# InputCircuitsAndSupply.net
KiCad netlist of a schematic drawn in Altium Designer
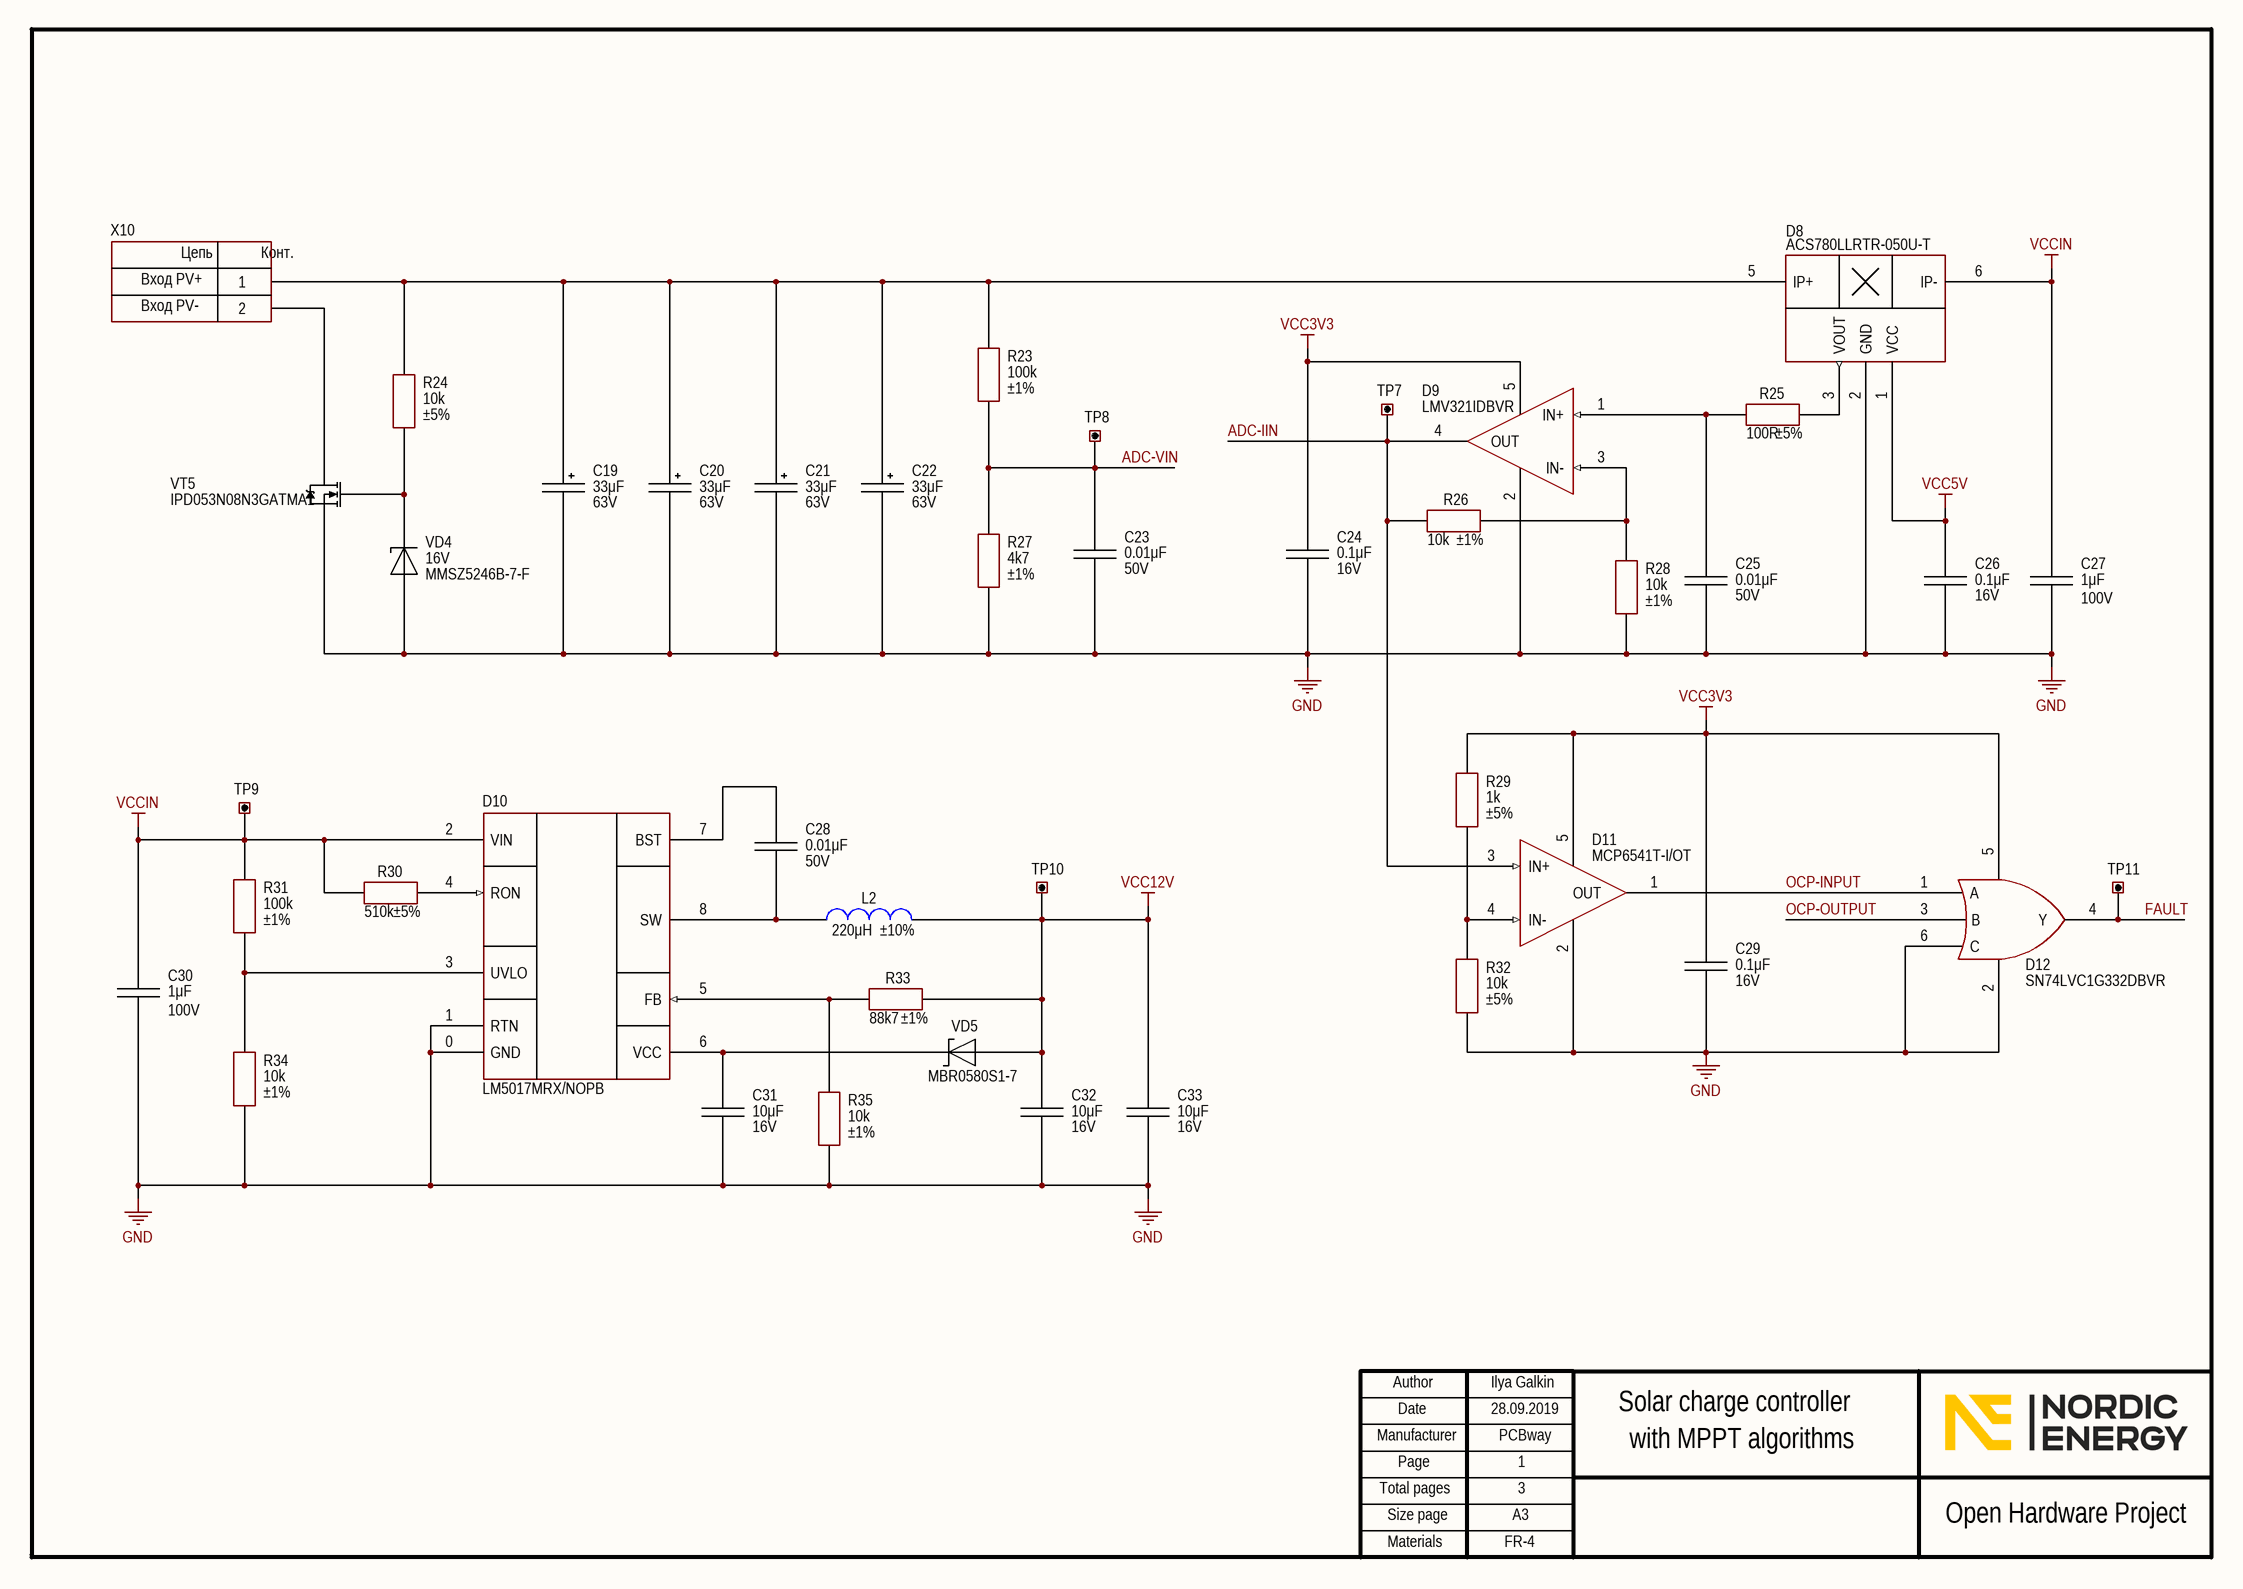
[diagram p0: InputCircuitsAndSupply.SchDoc]

(export (version "E")
  (design (tool "Eeschema 10.0.6"))
  (components
    (comp (ref "C19")
      (value "33μF")
      (footprint "CAP: D8C3.5H12")
      (fields
        (field (name "MANUFACTURER") "Panasonic")
        (field (name "PARTNUMBER") "63SXE33M")
        (field (name "VALUEMANUFACTURERPARTNUMBER") "Aluminium capacitor, 33μF, 63V, ±20%, 25mOhm, 12x8x3.5 mm, -55...+105°C")
        (field (name "VOLTAGE") "63V")
      )
      (libsource (lib "Capacitor") (part "Aluminium"))
    )
    (comp (ref "C20")
      (value "33μF")
      (footprint "CAP: D8C3.5H12")
      (fields
        (field (name "MANUFACTURER") "Panasonic")
        (field (name "PARTNUMBER") "63SXE33M")
        (field (name "VALUEMANUFACTURERPARTNUMBER") "Aluminium capacitor, 33μF, 63V, ±20%, 25mOhm, 12x8x3.5 mm, -55...+105°C")
        (field (name "VOLTAGE") "63V")
      )
      (libsource (lib "Capacitor") (part "Aluminium"))
    )
    (comp (ref "C21")
      (value "33μF")
      (footprint "CAP: D8C3.5H12")
      (fields
        (field (name "MANUFACTURER") "Panasonic")
        (field (name "PARTNUMBER") "63SXE33M")
        (field (name "VALUEMANUFACTURERPARTNUMBER") "Aluminium capacitor, 33μF, 63V, ±20%, 25mOhm, 12x8x3.5 mm, -55...+105°C")
        (field (name "VOLTAGE") "63V")
      )
      (libsource (lib "Capacitor") (part "Aluminium"))
    )
    (comp (ref "C22")
      (value "33μF")
      (footprint "CAP: D8C3.5H12")
      (fields
        (field (name "MANUFACTURER") "Panasonic")
        (field (name "PARTNUMBER") "63SXE33M")
        (field (name "VALUEMANUFACTURERPARTNUMBER") "Aluminium capacitor, 33μF, 63V, ±20%, 25mOhm, 12x8x3.5 mm, -55...+105°C")
        (field (name "VOLTAGE") "63V")
      )
      (libsource (lib "Capacitor") (part "Aluminium"))
    )
    (comp (ref "C23")
      (value "0.01μF")
      (footprint "CAP: 0805")
      (fields
        (field (name "MANUFACTURER") "Yageo")
        (field (name "PARTNUMBER") "CC0805KRX7R9BB103")
        (field (name "VALUEMANUFACTURERPARTNUMBER") "Ceramic capacitor, 0.01μF, X7R, ±10%, 50V, 0805, -55...+125°C")
        (field (name "VOLTAGE") "50V")
      )
      (libsource (lib "Capacitor") (part "Ceramic_0805"))
    )
    (comp (ref "C24")
      (value "0.1μF")
      (footprint "CAP: 0805")
      (fields
        (field (name "MANUFACTURER") "Yageo")
        (field (name "PARTNUMBER") "CC0805KRX7R7BB104")
        (field (name "VALUEMANUFACTURERPARTNUMBER") "Ceramic capacitor, 0.1μF, X7R, ±10%, 16V, 0805, -55...+125°C")
        (field (name "VOLTAGE") "16V")
      )
      (libsource (lib "Capacitor") (part "Ceramic_0805"))
    )
    (comp (ref "C25")
      (value "0.01μF")
      (footprint "CAP: 0805")
      (fields
        (field (name "MANUFACTURER") "Yageo")
        (field (name "PARTNUMBER") "CC0805KRX7R9BB103")
        (field (name "VALUEMANUFACTURERPARTNUMBER") "Ceramic capacitor, 0.01μF, X7R, ±10%, 50V, 0805, -55...+125°C")
        (field (name "VOLTAGE") "50V")
      )
      (libsource (lib "Capacitor") (part "Ceramic_0805"))
    )
    (comp (ref "C26")
      (value "0.1μF")
      (footprint "CAP: 0805")
      (fields
        (field (name "MANUFACTURER") "Yageo")
        (field (name "PARTNUMBER") "CC0805KRX7R7BB104")
        (field (name "VALUEMANUFACTURERPARTNUMBER") "Ceramic capacitor, 0.1μF, X7R, ±10%, 16V, 0805, -55...+125°C")
        (field (name "VOLTAGE") "16V")
      )
      (libsource (lib "Capacitor") (part "Ceramic_0805"))
    )
    (comp (ref "C27")
      (value "1μF")
      (footprint "CAP: 1206")
      (fields
        (field (name "MANUFACTURER") "Samsung")
        (field (name "PARTNUMBER") "CL31B105KCHNNNE")
        (field (name "VALUEMANUFACTURERPARTNUMBER") "Ceramic capacitor, 1μF, X7R, ±10%, 100V, 1206, -55...+125°C")
        (field (name "VOLTAGE") "100V")
      )
      (libsource (lib "Capacitor") (part "Ceramic_1206"))
    )
    (comp (ref "C28")
      (value "0.01μF")
      (footprint "CAP: 0805")
      (fields
        (field (name "MANUFACTURER") "Yageo")
        (field (name "PARTNUMBER") "CC0805KRX7R9BB103")
        (field (name "VALUEMANUFACTURERPARTNUMBER") "Ceramic capacitor, 0.01μF, X7R, ±10%, 50V, 0805, -55...+125°C")
        (field (name "VOLTAGE") "50V")
      )
      (libsource (lib "Capacitor") (part "Ceramic_0805"))
    )
    (comp (ref "C29")
      (value "0.1μF")
      (footprint "CAP: 0805")
      (fields
        (field (name "MANUFACTURER") "Yageo")
        (field (name "PARTNUMBER") "CC0805KRX7R7BB104")
        (field (name "VALUEMANUFACTURERPARTNUMBER") "Ceramic capacitor, 0.1μF, X7R, ±10%, 16V, 0805, -55...+125°C")
        (field (name "VOLTAGE") "16V")
      )
      (libsource (lib "Capacitor") (part "Ceramic_0805"))
    )
    (comp (ref "C30")
      (value "1μF")
      (footprint "CAP: 1206")
      (fields
        (field (name "MANUFACTURER") "Samsung")
        (field (name "PARTNUMBER") "CL31B105KCHNNNE")
        (field (name "VALUEMANUFACTURERPARTNUMBER") "Ceramic capacitor, 1μF, X7R, ±10%, 100V, 1206, -55...+125°C")
        (field (name "VOLTAGE") "100V")
      )
      (libsource (lib "Capacitor") (part "Ceramic_1206"))
    )
    (comp (ref "C31")
      (value "10μF")
      (footprint "CAP: 0805")
      (fields
        (field (name "MANUFACTURER") "Samsung")
        (field (name "PARTNUMBER") "CL21B106KOQNNNG")
        (field (name "VALUEMANUFACTURERPARTNUMBER") "Ceramic capacitor, 10μF, X7R, ±10%, 16V, 0805, -55...+125°C")
        (field (name "VOLTAGE") "16V")
      )
      (libsource (lib "Capacitor") (part "Ceramic_0805"))
    )
    (comp (ref "C32")
      (value "10μF")
      (footprint "CAP: 0805")
      (fields
        (field (name "MANUFACTURER") "Samsung")
        (field (name "PARTNUMBER") "CL21B106KOQNNNG")
        (field (name "VALUEMANUFACTURERPARTNUMBER") "Ceramic capacitor, 10μF, X7R, ±10%, 16V, 0805, -55...+125°C")
        (field (name "VOLTAGE") "16V")
      )
      (libsource (lib "Capacitor") (part "Ceramic_0805"))
    )
    (comp (ref "C33")
      (value "10μF")
      (footprint "CAP: 0805")
      (fields
        (field (name "MANUFACTURER") "Samsung")
        (field (name "PARTNUMBER") "CL21B106KOQNNNG")
        (field (name "VALUEMANUFACTURERPARTNUMBER") "Ceramic capacitor, 10μF, X7R, ±10%, 16V, 0805, -55...+125°C")
        (field (name "VOLTAGE") "16V")
      )
      (libsource (lib "Capacitor") (part "Ceramic_0805"))
    )
    (comp (ref "D8")
      (value "~")
      (footprint "SENSOR: ACS781")
      (description "Current sensors")
      (fields
        (field (name "MANUFACTURER") "Allegro MicroSystems")
        (field (name "VALUEMANUFACTURERPARTNUMBER") "IC current sensors, 50A, ±1.5%, 120 kHz, 60mV/A, -40...+150°C, 7-PSOF")
        (field (name "PARTNUMBER") "ACS780LLRTR-050U-T")
      )
      (libsource (lib "IC. Sensor") (part "ACS780"))
    )
    (comp (ref "D9")
      (value "~")
      (footprint "SOT23-5")
      (description "OP amplifier")
      (fields
        (field (name "MANUFACTURER") "Texas Instruments")
        (field (name "VALUEMANUFACTURERPARTNUMBER") "IC op amplifier, Rail-to-Rail, 1 MHz, 2.7...5.5V, -40...+125°C, SOT23-5")
        (field (name "PARTNUMBER") "LMV321IDBVR")
      )
      (libsource (lib "IC. Amplifier") (part "LMV321IDBVR"))
    )
    (comp (ref "D10")
      (value "~")
      (footprint "8-SOIC-PAD")
      (description "Buck converter")
      (fields
        (field (name "MANUFACTURER") "Texas Instruments")
        (field (name "VALUEMANUFACTURERPARTNUMBER") "DC/DC buck converter, input 7.5...100V, 1MHz, output 1.225...90V, 0.6A, -40...+125°C, 8-SOIC")
        (field (name "PARTNUMBER") "LM5017MRX/NOPB")
      )
      (libsource (lib "IC. Power supply") (part "LM5017MRX"))
    )
    (comp (ref "D11")
      (value "~")
      (footprint "SOT23-5")
      (description "Comparator")
      (fields
        (field (name "MANUFACTURER") "Microchip Technology")
        (field (name "VALUEMANUFACTURERPARTNUMBER") "IC comparator, Rail-to-Rail, 1.6...5.5V, -40...+85°C, SOT23-5")
        (field (name "PARTNUMBER") "MCP6541T-I/OT")
      )
      (libsource (lib "IC. Comparator") (part "MCP6541T-I/OT"))
    )
    (comp (ref "D12")
      (value "~")
      (footprint "SOT23-6")
      (description "OR")
      (fields
        (field (name "MANUFACTURER") "Texas Instruments")
        (field (name "VALUEMANUFACTURERPARTNUMBER") "IC logic OR, 1.65...5.5V, -40...+125°C, SOT23-6")
        (field (name "PARTNUMBER") "SN74LVC1G332DBVR")
      )
      (libsource (lib "IC. Logic") (part "SN74LVC1G332DBVR"))
    )
    (comp (ref "L2")
      (value "220μH")
      (footprint "IND: SDR0805")
      (fields
        (field (name "MANUFACTURER") "Bourns")
        (field (name "PARTNUMBER") "SDR0805-221KL")
        (field (name "VALUEMANUFACTURERPARTNUMBER") "Fixed inductor, 220μH, ±10%, SDR0805, 490mA, -40...+125°C")
        (field (name "TOLERANCE") "±10%")
      )
      (libsource (lib "Inductor") (part "Inductor_SDR0805"))
    )
    (comp (ref "R23")
      (value "100k")
      (footprint "RES: 0805")
      (fields
        (field (name "MANUFACTURER") "Yageo")
        (field (name "PARTNUMBER") "RC0805FR-07100KL")
        (field (name "VALUEMANUFACTURERPARTNUMBER") "Resistor film, 100k, ±1%, 0805, 0.125W, -55...+125°C")
        (field (name "TOLERANCE") "±1%")
      )
      (libsource (lib "Resistor") (part "Resistor_0805"))
    )
    (comp (ref "R24")
      (value "10k")
      (footprint "RES: 0805")
      (fields
        (field (name "MANUFACTURER") "Yageo")
        (field (name "PARTNUMBER") "RC0805JR-0710KL")
        (field (name "VALUEMANUFACTURERPARTNUMBER") "Resistor film, 10k, ±5%, 0805, 0.125W, -55...+125°C")
        (field (name "TOLERANCE") "±5%")
      )
      (libsource (lib "Resistor") (part "Resistor_0805"))
    )
    (comp (ref "R25")
      (value "100R")
      (footprint "RES: 0805")
      (fields
        (field (name "MANUFACTURER") "Yageo")
        (field (name "PARTNUMBER") "RC0805JR-07100RL")
        (field (name "VALUEMANUFACTURERPARTNUMBER") "Resistor film, 100R, ±5%, 0805, 0.125W, -55...+125°C")
        (field (name "TOLERANCE") "±5%")
      )
      (libsource (lib "") (part "Resistor_0805_1"))
    )
    (comp (ref "R26")
      (value "10k")
      (footprint "RES: 0805")
      (fields
        (field (name "MANUFACTURER") "Yageo")
        (field (name "PARTNUMBER") "RC0805FR-0710KL")
        (field (name "VALUEMANUFACTURERPARTNUMBER") "Resistor film, 10k, ±1%, 0805, 0.125W, -55...+125°C")
        (field (name "TOLERANCE") "±1%")
      )
      (libsource (lib "") (part "Resistor_0805_1"))
    )
    (comp (ref "R27")
      (value "4k7")
      (footprint "RES: 0805")
      (fields
        (field (name "MANUFACTURER") "Yageo")
        (field (name "PARTNUMBER") "RC0805FR-074K7L")
        (field (name "VALUEMANUFACTURERPARTNUMBER") "Resistor film, 4k7, ±1%, 0805, 0.125W, -55...+125°C")
        (field (name "TOLERANCE") "±1%")
      )
      (libsource (lib "Resistor") (part "Resistor_0805"))
    )
    (comp (ref "R28")
      (value "10k")
      (footprint "RES: 0805")
      (fields
        (field (name "MANUFACTURER") "Yageo")
        (field (name "PARTNUMBER") "RC0805FR-0710KL")
        (field (name "VALUEMANUFACTURERPARTNUMBER") "Resistor film, 10k, ±1%, 0805, 0.125W, -55...+125°C")
        (field (name "TOLERANCE") "±1%")
      )
      (libsource (lib "Resistor") (part "Resistor_0805"))
    )
    (comp (ref "R29")
      (value "1k")
      (footprint "RES: 0805")
      (fields
        (field (name "MANUFACTURER") "Yageo")
        (field (name "PARTNUMBER") "RC0805JR-071KL")
        (field (name "VALUEMANUFACTURERPARTNUMBER") "Resistor film, 1k, ±5%, 0805, 0.125W, -55...+125°C")
        (field (name "TOLERANCE") "±5%")
      )
      (libsource (lib "Resistor") (part "Resistor_0805"))
    )
    (comp (ref "R30")
      (value "510k")
      (footprint "RES: 0805")
      (fields
        (field (name "MANUFACTURER") "Yageo")
        (field (name "PARTNUMBER") "RC0805JR-07510KL")
        (field (name "VALUEMANUFACTURERPARTNUMBER") "Resistor film, 510k, ±5%, 0805, 0.125W, -55...+125°C")
        (field (name "TOLERANCE") "±5%")
      )
      (libsource (lib "") (part "Resistor_0805_1"))
    )
    (comp (ref "R31")
      (value "100k")
      (footprint "RES: 0805")
      (fields
        (field (name "MANUFACTURER") "Yageo")
        (field (name "PARTNUMBER") "RC0805FR-07100KL")
        (field (name "VALUEMANUFACTURERPARTNUMBER") "Resistor film, 100k, ±1%, 0805, 0.125W, -55...+125°C")
        (field (name "TOLERANCE") "±1%")
      )
      (libsource (lib "") (part "Resistor_0805_2"))
    )
    (comp (ref "R32")
      (value "10k")
      (footprint "RES: 0805")
      (fields
        (field (name "MANUFACTURER") "Yageo")
        (field (name "PARTNUMBER") "RC0805JR-0710KL")
        (field (name "VALUEMANUFACTURERPARTNUMBER") "Resistor film, 10k, ±5%, 0805, 0.125W, -55...+125°C")
        (field (name "TOLERANCE") "±5%")
      )
      (libsource (lib "Resistor") (part "Resistor_0805"))
    )
    (comp (ref "R33")
      (value "88k7")
      (footprint "RES: 0805")
      (fields
        (field (name "MANUFACTURER") "Yageo")
        (field (name "PARTNUMBER") "RC0805FR-0788K7L")
        (field (name "VALUEMANUFACTURERPARTNUMBER") "Resistor film, 88k7, ±1%, 0805, 0.125W, -55...+125°C")
        (field (name "TOLERANCE") "±1%")
      )
      (libsource (lib "") (part "Resistor_0805_1"))
    )
    (comp (ref "R34")
      (value "10k")
      (footprint "RES: 0805")
      (fields
        (field (name "MANUFACTURER") "Yageo")
        (field (name "PARTNUMBER") "RC0805FR-0710KL")
        (field (name "VALUEMANUFACTURERPARTNUMBER") "Resistor film, 10k, ±1%, 0805, 0.125W, -55...+125°C")
        (field (name "TOLERANCE") "±1%")
      )
      (libsource (lib "Resistor") (part "Resistor_0805"))
    )
    (comp (ref "R35")
      (value "10k")
      (footprint "RES: 0805")
      (fields
        (field (name "MANUFACTURER") "Yageo")
        (field (name "PARTNUMBER") "RC0805FR-0710KL")
        (field (name "VALUEMANUFACTURERPARTNUMBER") "Resistor film, 10k, ±1%, 0805, 0.125W, -55...+125°C")
        (field (name "TOLERANCE") "±1%")
      )
      (libsource (lib "Resistor") (part "Resistor_0805"))
    )
    (comp (ref "TP7")
      (value "~")
      (footprint "CON: 5004 (Keystone)")
      (fields
        (field (name "MANUFACTURER") "Keystone")
        (field (name "VALUEMANUFACTURERPARTNUMBER") "Test point, Keystone, 5001")
        (field (name "PARTNUMBER") "5001")
      )
      (libsource (lib "Connector") (part "Connector_Test_Point"))
    )
    (comp (ref "TP8")
      (value "~")
      (footprint "CON: 5004 (Keystone)")
      (fields
        (field (name "MANUFACTURER") "Keystone")
        (field (name "VALUEMANUFACTURERPARTNUMBER") "Test point, Keystone, 5001")
        (field (name "PARTNUMBER") "5001")
      )
      (libsource (lib "Connector") (part "Connector_Test_Point"))
    )
    (comp (ref "TP9")
      (value "~")
      (footprint "CON: 5001 (Keystone)")
      (fields
        (field (name "MANUFACTURER") "Keystone")
        (field (name "VALUEMANUFACTURERPARTNUMBER") "Test point, Keystone, 5001")
        (field (name "PARTNUMBER") "5001")
      )
      (libsource (lib "Connector") (part "Connector_Test_Point"))
    )
    (comp (ref "TP10")
      (value "~")
      (footprint "CON: 5001 (Keystone)")
      (fields
        (field (name "MANUFACTURER") "Keystone")
        (field (name "VALUEMANUFACTURERPARTNUMBER") "Test point, Keystone, 5001")
        (field (name "PARTNUMBER") "5001")
      )
      (libsource (lib "Connector") (part "Connector_Test_Point"))
    )
    (comp (ref "TP11")
      (value "~")
      (footprint "CON: 5001 (Keystone)")
      (fields
        (field (name "MANUFACTURER") "Keystone")
        (field (name "VALUEMANUFACTURERPARTNUMBER") "Test point, Keystone, 5001")
        (field (name "PARTNUMBER") "5001")
      )
      (libsource (lib "Connector") (part "Connector_Test_Point"))
    )
    (comp (ref "VD4")
      (value "~")
      (footprint "DIODE: SOD123")
      (fields
        (field (name "MANUFACTURER") "Diodes Incorporated")
        (field (name "VALUEMANUFACTURERPARTNUMBER") "Zener diode, 16V, 500mW, 0.9V, 17Ohm, SOD-123, -65...+150°C")
        (field (name "VOLTAGE") "16V")
        (field (name "PARTNUMBER") "MMSZ5246B-7-F")
      )
      (libsource (lib "Diode") (part "Zener_single"))
    )
    (comp (ref "VD5")
      (value "~")
      (footprint "DIODE: SOD123")
      (fields
        (field (name "MANUFACTURER") "Diodes Incorporated")
        (field (name "VALUEMANUFACTURERPARTNUMBER") "Schottky diode, 80V, 500mA, 1V, 15pF, SOD-123, -55...+150°C")
        (field (name "VOLTAGE") "80V")
        (field (name "PARTNUMBER") "MBR0580S1-7")
      )
      (libsource (lib "Diode") (part "Schottky_single"))
    )
    (comp (ref "VT5")
      (value "~")
      (footprint "DPAK")
      (fields
        (field (name "MANUFACTURER") "Infineon Technologies")
        (field (name "VALUEMANUFACTURERPARTNUMBER") "MOSFET N-channel transistor, 80V, 90A, 69nC, 150W, 5.3mOhm, 4750pF, Dpak, -55...+150°C")
        (field (name "PARTNUMBER") "IPD053N08N3GATMA1")
      )
      (libsource (lib "Transistor") (part "MOSFET_N_132"))
    )
    (comp (ref "X10")
      (value "~")
      (footprint "CON: 6PCV-02-006")
      (fields
        (field (name "MANUFACTURER") "TE Connectivity")
        (field (name "VALUEMANUFACTURERPARTNUMBER") "Connector, 2pin, 9.53mm, 300VAC, 25A")
        (field (name "PARTNUMBER") "6PCV-02-006")
      )
      (libsource (lib "Connector") (part "Connector_6PCV-02"))
    )
  )
  (nets
    (net (code "1") (name "/ADC-IIN") (class "Default")
      (node (ref "D11") (pin "3") (pinfunction "IN+_3") (pintype "input"))
      (node (ref "D9") (pin "4") (pinfunction "OUT_4") (pintype "power_in"))
      (node (ref "R26") (pin "1") (pinfunction "1_1") (pintype "passive"))
      (node (ref "TP7") (pin "1") (pinfunction "1_1") (pintype "passive"))
    )
    (net (code "2") (name "/ADC-VIN") (class "Default")
      (node (ref "C23") (pin "2") (pinfunction "2_2") (pintype "power_in"))
      (node (ref "R23") (pin "2") (pinfunction "2_2") (pintype "passive"))
      (node (ref "R27") (pin "1") (pinfunction "1_1") (pintype "passive"))
      (node (ref "TP8") (pin "1") (pinfunction "1_1") (pintype "passive"))
    )
    (net (code "3") (name "/FAULT") (class "Default")
      (node (ref "D12") (pin "4") (pinfunction "Y_4") (pintype "passive"))
      (node (ref "TP11") (pin "1") (pinfunction "1_1") (pintype "passive"))
    )
    (net (code "4") (name "/OCP-INPUT") (class "Default")
      (node (ref "D11") (pin "1") (pinfunction "OUT_1") (pintype "power_in"))
      (node (ref "D12") (pin "1") (pinfunction "A_1") (pintype "passive"))
    )
    (net (code "5") (name "/OCP-OUTPUT") (class "Default")
      (node (ref "D12") (pin "3") (pinfunction "B_3") (pintype "passive"))
    )
    (net (code "6") (name "GND") (class "Default")
      (node (ref "C19") (pin "2") (pinfunction "2_2") (pintype "power_in"))
      (node (ref "C20") (pin "2") (pinfunction "2_2") (pintype "power_in"))
      (node (ref "C21") (pin "2") (pinfunction "2_2") (pintype "power_in"))
      (node (ref "C22") (pin "2") (pinfunction "2_2") (pintype "power_in"))
      (node (ref "C23") (pin "1") (pinfunction "1_1") (pintype "power_in"))
      (node (ref "C24") (pin "1") (pinfunction "1_1") (pintype "power_in"))
      (node (ref "C25") (pin "1") (pinfunction "1_1") (pintype "power_in"))
      (node (ref "C26") (pin "1") (pinfunction "1_1") (pintype "power_in"))
      (node (ref "C27") (pin "1") (pinfunction "1_1") (pintype "power_in"))
      (node (ref "C29") (pin "1") (pinfunction "1_1") (pintype "power_in"))
      (node (ref "C30") (pin "1") (pinfunction "1_1") (pintype "power_in"))
      (node (ref "C31") (pin "1") (pinfunction "1_1") (pintype "power_in"))
      (node (ref "C32") (pin "1") (pinfunction "1_1") (pintype "power_in"))
      (node (ref "C33") (pin "1") (pinfunction "1_1") (pintype "power_in"))
      (node (ref "D10") (pin "0") (pinfunction "GND_0") (pintype "passive"))
      (node (ref "D10") (pin "1") (pinfunction "RTN_1") (pintype "passive"))
      (node (ref "D11") (pin "2") (pinfunction "V-_2") (pintype "power_in"))
      (node (ref "D12") (pin "2") (pintype "passive"))
      (node (ref "D12") (pin "6") (pinfunction "C_6") (pintype "passive"))
      (node (ref "D8") (pin "2") (pinfunction "GND_2") (pintype "passive"))
      (node (ref "D9") (pin "2") (pinfunction "V-_2") (pintype "power_in"))
      (node (ref "R27") (pin "2") (pinfunction "2_2") (pintype "passive"))
      (node (ref "R28") (pin "2") (pinfunction "2_2") (pintype "passive"))
      (node (ref "R32") (pin "2") (pinfunction "2_2") (pintype "passive"))
      (node (ref "R34") (pin "2") (pinfunction "2_2") (pintype "passive"))
      (node (ref "R35") (pin "2") (pinfunction "2_2") (pintype "passive"))
      (node (ref "VD4") (pin "1") (pinfunction "A_1") (pintype "passive"))
      (node (ref "VT5") (pin "2") (pinfunction "S_2") (pintype "passive"))
    )
    (net (code "7") (name "Net-(D8-IP+)") (class "Default")
      (node (ref "C19") (pin "1") (pinfunction "1_1") (pintype "power_in"))
      (node (ref "C20") (pin "1") (pinfunction "1_1") (pintype "power_in"))
      (node (ref "C21") (pin "1") (pinfunction "1_1") (pintype "power_in"))
      (node (ref "C22") (pin "1") (pinfunction "1_1") (pintype "power_in"))
      (node (ref "D8") (pin "5") (pinfunction "IP+_5") (pintype "passive"))
      (node (ref "R23") (pin "1") (pinfunction "1_1") (pintype "passive"))
      (node (ref "R24") (pin "1") (pinfunction "1_1") (pintype "passive"))
      (node (ref "X10") (pin "1") (pinfunction "1_1") (pintype "passive"))
    )
    (net (code "8") (name "Net-(D8-VOUT)") (class "Default")
      (node (ref "D8") (pin "3") (pinfunction "VOUT_3") (pintype "output"))
      (node (ref "R25") (pin "2") (pinfunction "2_2") (pintype "passive"))
    )
    (net (code "9") (name "Net-(D9-IN+)") (class "Default")
      (node (ref "C25") (pin "2") (pinfunction "2_2") (pintype "power_in"))
      (node (ref "D9") (pin "1") (pinfunction "IN+_1") (pintype "input"))
      (node (ref "R25") (pin "1") (pinfunction "1_1") (pintype "passive"))
    )
    (net (code "10") (name "Net-(D9-IN-)") (class "Default")
      (node (ref "D9") (pin "3") (pinfunction "IN-_3") (pintype "input"))
      (node (ref "R26") (pin "2") (pinfunction "2_2") (pintype "passive"))
      (node (ref "R28") (pin "1") (pinfunction "1_1") (pintype "passive"))
    )
    (net (code "11") (name "Net-(D10-BST)") (class "Default")
      (node (ref "C28") (pin "2") (pinfunction "2_2") (pintype "power_in"))
      (node (ref "D10") (pin "7") (pinfunction "BST_7") (pintype "passive"))
    )
    (net (code "12") (name "Net-(D10-FB)") (class "Default")
      (node (ref "D10") (pin "5") (pinfunction "FB_5") (pintype "input"))
      (node (ref "R33") (pin "1") (pinfunction "1_1") (pintype "passive"))
      (node (ref "R35") (pin "1") (pinfunction "1_1") (pintype "passive"))
    )
    (net (code "13") (name "Net-(D10-RON)") (class "Default")
      (node (ref "D10") (pin "4") (pinfunction "RON_4") (pintype "input"))
      (node (ref "R30") (pin "2") (pinfunction "2_2") (pintype "passive"))
    )
    (net (code "14") (name "Net-(D10-SW)") (class "Default")
      (node (ref "C28") (pin "1") (pinfunction "1_1") (pintype "power_in"))
      (node (ref "D10") (pin "8") (pinfunction "SW_8") (pintype "passive"))
      (node (ref "L2") (pin "2") (pinfunction "2_2") (pintype "passive"))
    )
    (net (code "15") (name "Net-(D10-UVLO)") (class "Default")
      (node (ref "D10") (pin "3") (pinfunction "UVLO_3") (pintype "passive"))
      (node (ref "R31") (pin "1") (pinfunction "1_1") (pintype "passive"))
      (node (ref "R34") (pin "1") (pinfunction "1_1") (pintype "passive"))
    )
    (net (code "16") (name "Net-(D10-VCC)") (class "Default")
      (node (ref "C31") (pin "2") (pinfunction "2_2") (pintype "power_in"))
      (node (ref "D10") (pin "6") (pinfunction "VCC_6") (pintype "passive"))
      (node (ref "VD5") (pin "2") (pinfunction "2_2") (pintype "passive"))
    )
    (net (code "17") (name "Net-(D11-IN-)") (class "Default")
      (node (ref "D11") (pin "4") (pinfunction "IN-_4") (pintype "input"))
      (node (ref "R29") (pin "2") (pinfunction "2_2") (pintype "passive"))
      (node (ref "R32") (pin "1") (pinfunction "1_1") (pintype "passive"))
    )
    (net (code "18") (name "Net-(VD4-C)") (class "Default")
      (node (ref "R24") (pin "2") (pinfunction "2_2") (pintype "passive"))
      (node (ref "VD4") (pin "2") (pinfunction "C_2") (pintype "passive"))
      (node (ref "VT5") (pin "1") (pinfunction "G_1") (pintype "passive"))
    )
    (net (code "19") (name "Net-(VT5-D)") (class "Default")
      (node (ref "VT5") (pin "3") (pinfunction "D_3") (pintype "passive"))
      (node (ref "X10") (pin "2") (pinfunction "2_2") (pintype "passive"))
    )
    (net (code "20") (name "VCC3V3") (class "Default")
      (node (ref "C24") (pin "2") (pinfunction "2_2") (pintype "power_in"))
      (node (ref "C29") (pin "2") (pinfunction "2_2") (pintype "power_in"))
      (node (ref "D11") (pin "5") (pinfunction "V+_5") (pintype "power_in"))
      (node (ref "D12") (pin "5") (pintype "passive"))
      (node (ref "D9") (pin "5") (pinfunction "V+_5") (pintype "power_in"))
      (node (ref "R29") (pin "1") (pinfunction "1_1") (pintype "passive"))
    )
    (net (code "21") (name "VCC5V") (class "Default")
      (node (ref "C26") (pin "2") (pinfunction "2_2") (pintype "power_in"))
      (node (ref "D8") (pin "1") (pinfunction "VCC_1") (pintype "passive"))
    )
    (net (code "22") (name "VCC12V") (class "Default")
      (node (ref "C32") (pin "2") (pinfunction "2_2") (pintype "power_in"))
      (node (ref "C33") (pin "2") (pinfunction "2_2") (pintype "power_in"))
      (node (ref "L2") (pin "1") (pinfunction "1_1") (pintype "passive"))
      (node (ref "R33") (pin "2") (pinfunction "2_2") (pintype "passive"))
      (node (ref "TP10") (pin "1") (pinfunction "1_1") (pintype "passive"))
      (node (ref "VD5") (pin "1") (pinfunction "1_1") (pintype "passive"))
    )
    (net (code "23") (name "VCCIN") (class "Default")
      (node (ref "C27") (pin "2") (pinfunction "2_2") (pintype "power_in"))
      (node (ref "C30") (pin "2") (pinfunction "2_2") (pintype "power_in"))
      (node (ref "D10") (pin "2") (pinfunction "VIN_2") (pintype "passive"))
      (node (ref "D8") (pin "6") (pinfunction "IP-_6") (pintype "passive"))
      (node (ref "R30") (pin "1") (pinfunction "1_1") (pintype "passive"))
      (node (ref "R31") (pin "2") (pinfunction "2_2") (pintype "passive"))
      (node (ref "TP9") (pin "1") (pinfunction "1_1") (pintype "passive"))
    )
  )
)
